# MRCS-Hankscraft-Contact.net
KiCad netlist of a schematic drawn in EAGLE
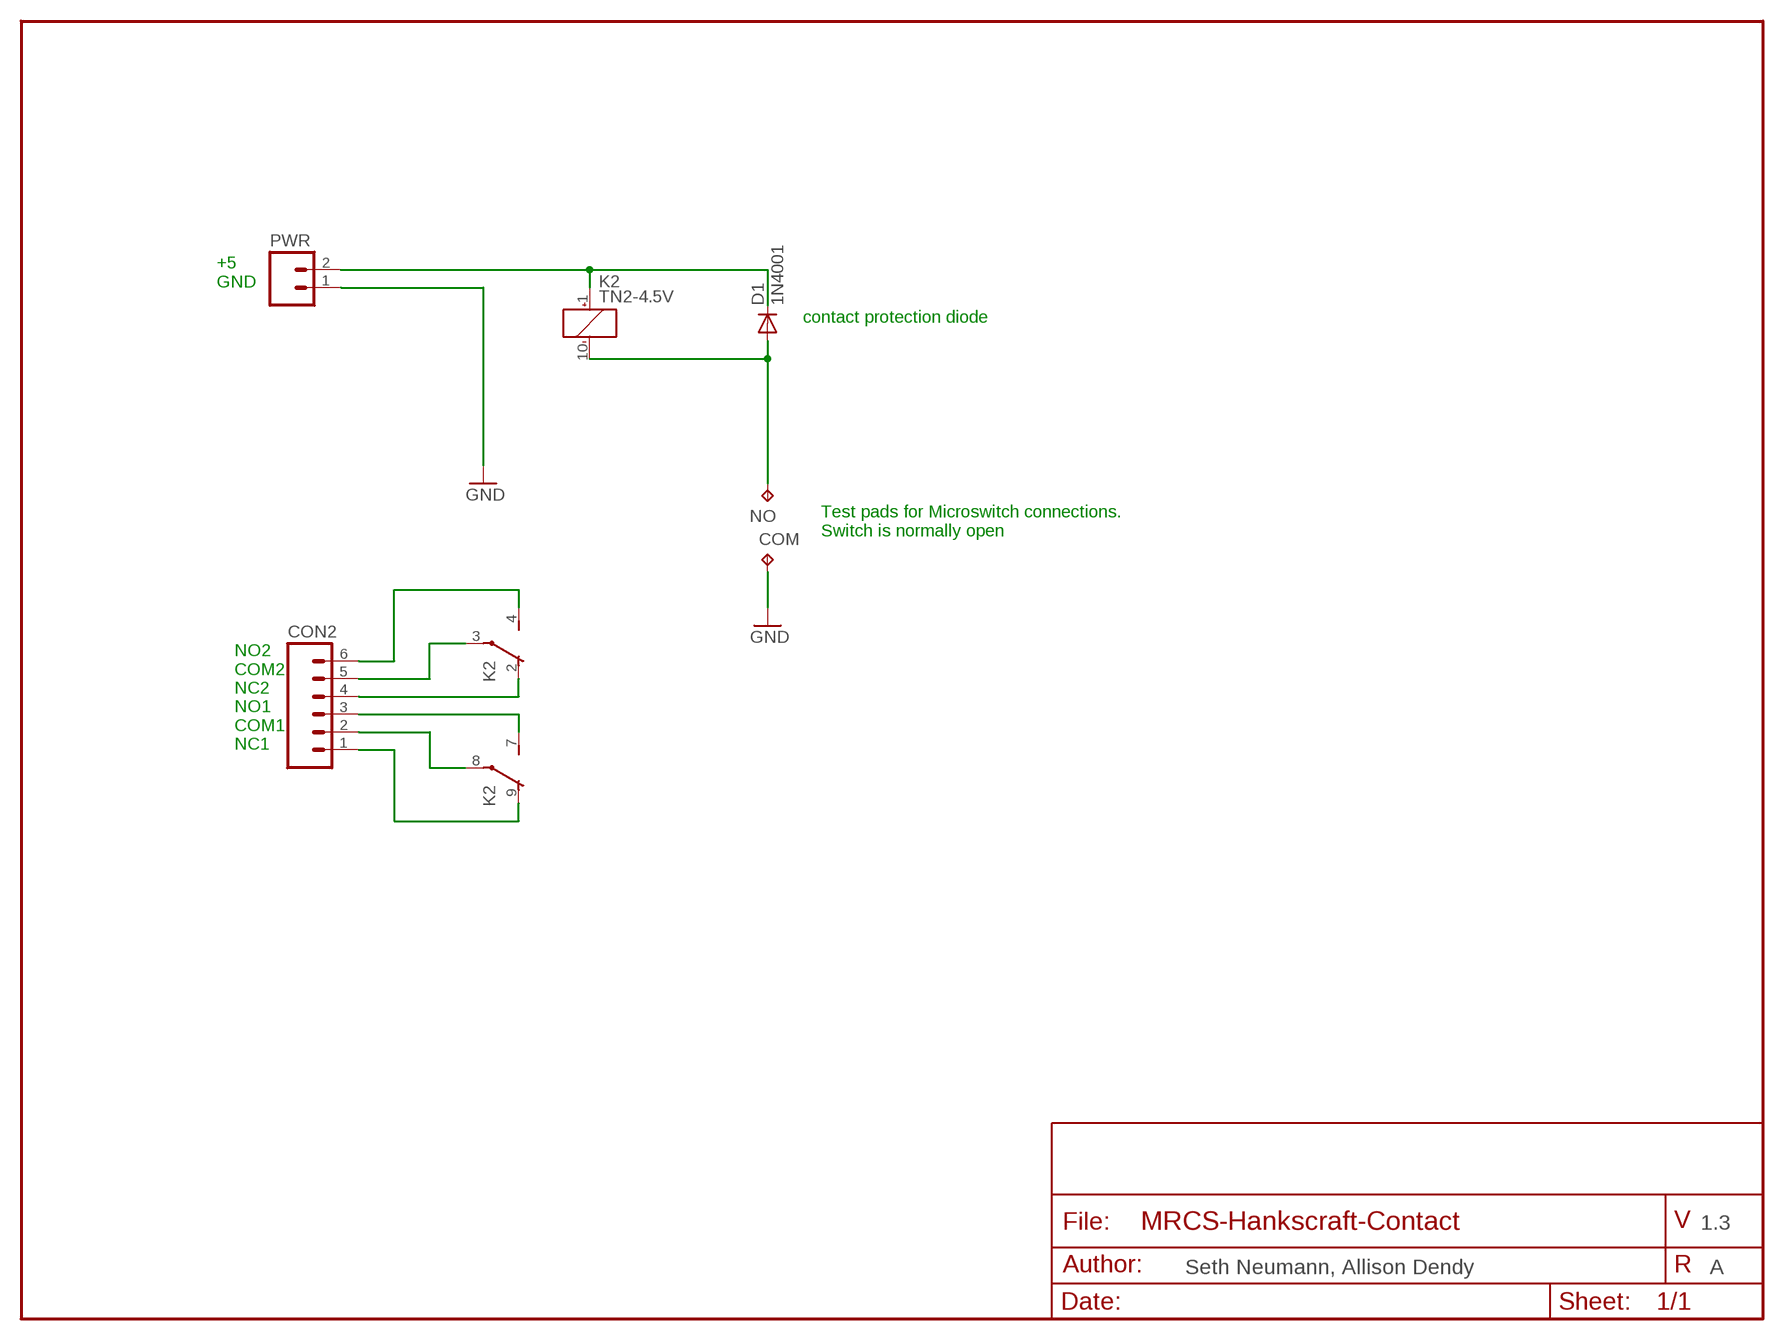
[diagram p0: schematic, sheet 1]

(export (version "E")
  (design (tool "Eeschema 10.0.6"))
  (components
    (comp (ref "COM")
      (value "TPPAD1-13")
      (footprint "eagle-import:P1-13")
      (libsource (lib "eagle-import") (part "TPPAD1-13"))
    )
    (comp (ref "CON2")
      (value "CONNECTOR-M06LOCK")
      (footprint "eagle-import:1X06_LOCK")
      (libsource (lib "eagle-import") (part "CONNECTOR-M06LOCK"))
    )
    (comp (ref "D1")
      (value "1N4001")
      (footprint "eagle-import:DIODE-1N4001")
      (libsource (lib "eagle-import") (part "DIODEPTH"))
    )
    (comp (ref "K2")
      (value "TN2-4.5V")
      (footprint "eagle-import:TN2")
      (fields (field (name "MF") "AROMAT/ MATSUSHITA"))
      (libsource (lib "eagle-import") (part "TN2?-4.5V"))
    )
    (comp (ref "NO")
      (value "TPPAD1-13")
      (footprint "eagle-import:P1-13")
      (libsource (lib "eagle-import") (part "TPPAD1-13"))
    )
    (comp (ref "PWR")
      (value "CONNECTOR-M021X02-LOCK")
      (footprint "eagle-import:1X02_LOCK")
      (libsource (lib "eagle-import") (part "CONNECTOR-M021X02-LOCK"))
    )
  )
  (nets
    (net (code "1") (name "GND") (class "Default")
      (node (ref "COM") (pin "TP") (pinfunction "TP_TP") (pintype "input"))
      (node (ref "PWR") (pin "1") (pinfunction "A_1") (pintype "passive"))
    )
    (net (code "2") (name "Net-(K2A-+)") (class "Default")
      (node (ref "D1") (pin "C") (pinfunction "C_C") (pintype "passive"))
      (node (ref "K2") (pin "1") (pinfunction "+_1") (pintype "passive"))
      (node (ref "PWR") (pin "2") (pinfunction "B_2") (pintype "passive"))
    )
    (net (code "3") (name "Net-(K2A--)") (class "Default")
      (node (ref "D1") (pin "A") (pinfunction "A_A") (pintype "passive"))
      (node (ref "K2") (pin "10") (pinfunction "-_10") (pintype "passive"))
      (node (ref "NO") (pin "TP") (pinfunction "TP_TP") (pintype "input"))
    )
    (net (code "4") (name "Net-(K2B-O)") (class "Default")
      (node (ref "CON2") (pin "4") (pinfunction "4_4") (pintype "passive"))
      (node (ref "K2") (pin "2") (pinfunction "O_2") (pintype "passive"))
    )
    (net (code "5") (name "Net-(K2B-P)") (class "Default")
      (node (ref "CON2") (pin "5") (pinfunction "5_5") (pintype "passive"))
      (node (ref "K2") (pin "3") (pinfunction "P_3") (pintype "passive"))
    )
    (net (code "6") (name "Net-(K2B-S)") (class "Default")
      (node (ref "CON2") (pin "6") (pinfunction "6_6") (pintype "passive"))
      (node (ref "K2") (pin "4") (pinfunction "S_4") (pintype "passive"))
    )
    (net (code "7") (name "Net-(K2C-O)") (class "Default")
      (node (ref "CON2") (pin "1") (pinfunction "1_1") (pintype "passive"))
      (node (ref "K2") (pin "9") (pinfunction "O_9") (pintype "passive"))
    )
    (net (code "8") (name "Net-(K2C-P)") (class "Default")
      (node (ref "CON2") (pin "2") (pinfunction "2_2") (pintype "passive"))
      (node (ref "K2") (pin "8") (pinfunction "P_8") (pintype "passive"))
    )
    (net (code "9") (name "Net-(K2C-S)") (class "Default")
      (node (ref "CON2") (pin "3") (pinfunction "3_3") (pintype "passive"))
      (node (ref "K2") (pin "7") (pinfunction "S_7") (pintype "passive"))
    )
  )
)
